# Thermostat.net
KiCad netlist of a schematic drawn in Altium Designer
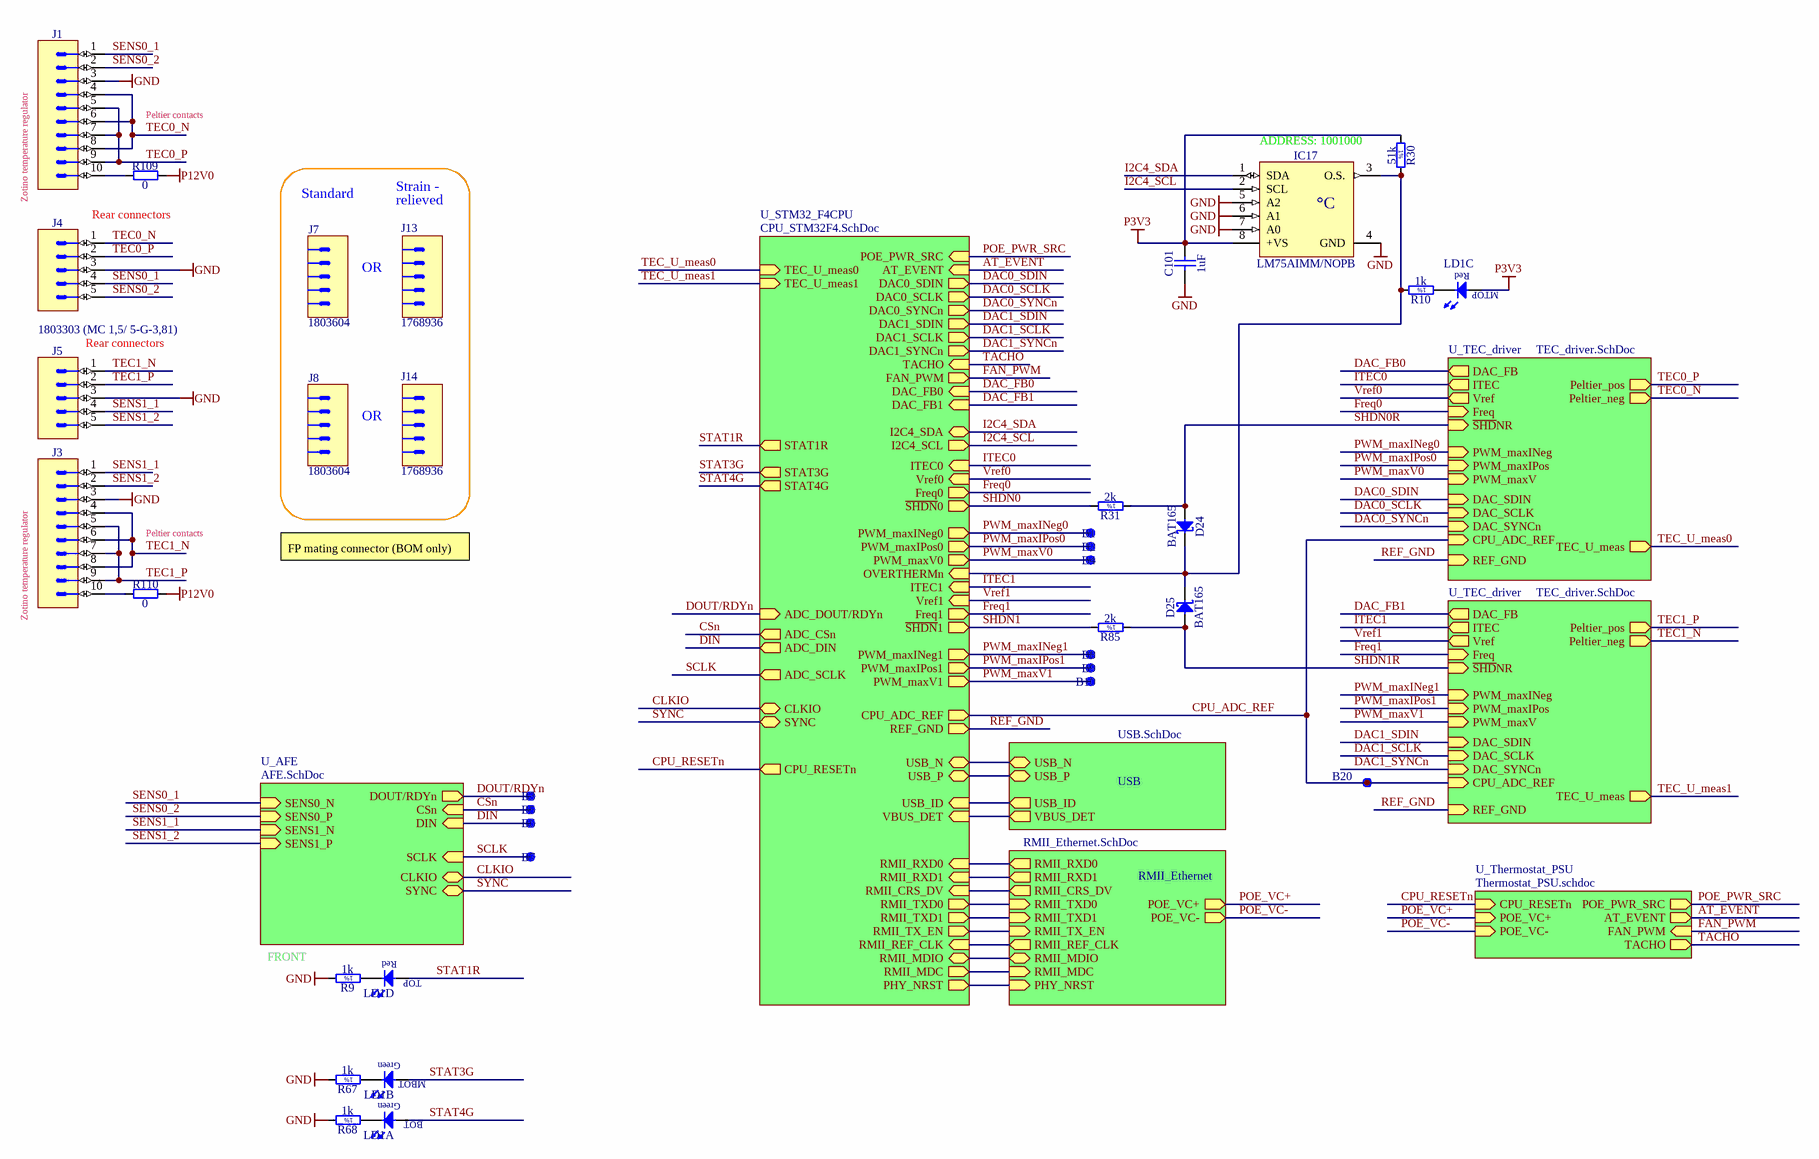
[diagram p0: Thermostat.schdoc]

(export (version "E")
  (design (tool "Eeschema 10.0.6"))
  (components
    (comp (ref "B1")
      (value "SMD Pad")
      (footprint "C100")
      (description "Through Hole Pad")
      (fields (field (name "PART NUMBER") "SMD_PAD_D1MM") (field (name "AUTHOR") "CERN DEM JLC"))
      (libsource (lib "Eletro-mechanical") (part "Single SMD Pad (Round)"))
    )
    (comp (ref "B2")
      (value "SMD Pad")
      (footprint "C100")
      (description "Through Hole Pad")
      (fields (field (name "PART NUMBER") "SMD_PAD_D1MM") (field (name "AUTHOR") "CERN DEM JLC"))
      (libsource (lib "Eletro-mechanical") (part "Single SMD Pad (Round)"))
    )
    (comp (ref "B3")
      (value "SMD Pad")
      (footprint "C100")
      (description "Through Hole Pad")
      (fields (field (name "PART NUMBER") "SMD_PAD_D1MM") (field (name "AUTHOR") "CERN DEM JLC"))
      (libsource (lib "Eletro-mechanical") (part "Single SMD Pad (Round)"))
    )
    (comp (ref "B4")
      (value "SMD Pad")
      (footprint "C100")
      (description "Through Hole Pad")
      (fields (field (name "PART NUMBER") "SMD_PAD_D1MM") (field (name "AUTHOR") "CERN DEM JLC"))
      (libsource (lib "Eletro-mechanical") (part "Single SMD Pad (Round)"))
    )
    (comp (ref "B5")
      (value "SMD Pad")
      (footprint "C100")
      (description "Through Hole Pad")
      (fields (field (name "PART NUMBER") "SMD_PAD_D1MM") (field (name "AUTHOR") "CERN DEM JLC"))
      (libsource (lib "Eletro-mechanical") (part "Single SMD Pad (Round)"))
    )
    (comp (ref "B6")
      (value "SMD Pad")
      (footprint "C100")
      (description "Through Hole Pad")
      (fields (field (name "PART NUMBER") "SMD_PAD_D1MM") (field (name "AUTHOR") "CERN DEM JLC"))
      (libsource (lib "Eletro-mechanical") (part "Single SMD Pad (Round)"))
    )
    (comp (ref "B7")
      (value "SMD Pad")
      (footprint "C100")
      (description "Through Hole Pad")
      (fields (field (name "PART NUMBER") "SMD_PAD_D1MM") (field (name "AUTHOR") "CERN DEM JLC"))
      (libsource (lib "Eletro-mechanical") (part "Single SMD Pad (Round)"))
    )
    (comp (ref "B8")
      (value "SMD Pad")
      (footprint "C100")
      (description "Through Hole Pad")
      (fields (field (name "PART NUMBER") "SMD_PAD_D1MM") (field (name "AUTHOR") "CERN DEM JLC"))
      (libsource (lib "Eletro-mechanical") (part "Single SMD Pad (Round)"))
    )
    (comp (ref "B9")
      (value "SMD Pad")
      (footprint "C100")
      (description "Through Hole Pad")
      (fields (field (name "PART NUMBER") "SMD_PAD_D1MM") (field (name "AUTHOR") "CERN DEM JLC"))
      (libsource (lib "Eletro-mechanical") (part "Single SMD Pad (Round)"))
    )
    (comp (ref "B10")
      (value "SMD Pad")
      (footprint "C100")
      (description "Through Hole Pad")
      (fields (field (name "PART NUMBER") "SMD_PAD_D1MM") (field (name "AUTHOR") "CERN DEM JLC"))
      (libsource (lib "Eletro-mechanical") (part "Single SMD Pad (Round)"))
    )
    (comp (ref "B20")
      (value "SMD Pad")
      (footprint "C100")
      (description "Through Hole Pad")
      (fields (field (name "PART NUMBER") "SMD_PAD_D1MM") (field (name "AUTHOR") "CERN DEM JLC"))
      (libsource (lib "Eletro-mechanical") (part "Single SMD Pad (Round)"))
    )
    (comp (ref "C101")
      (value "1uF")
      (footprint "CAPC1608X87N")
      (description "Non-polarised capacitor")
      (fields
        (field (name "PART NUMBER") "CC0603_1UF_25V_10%_X7R")
        (field (name "VOLTAGE") "25V")
        (field (name "AUTHOR") "CERN DEM JLC")
      )
      (libsource (lib "Capacitors") (part "Capacitor - non polarized"))
    )
    (comp (ref "D24")
      (value "BAT165")
      (footprint "SOD2512X110N")
      (description "Schottky Diode")
      (fields
        (field (name "VOLTAGE") "40V")
        (field (name "POWER") "750mA")
        (field (name "AUTHOR") "CERN DEM JLC")
      )
      (libsource (lib "ICs And Semiconductors") (part "Diode Schottky"))
    )
    (comp (ref "D25")
      (value "BAT165")
      (footprint "SOD2512X110N")
      (description "Schottky Diode")
      (fields
        (field (name "VOLTAGE") "40V")
        (field (name "POWER") "750mA")
        (field (name "AUTHOR") "CERN DEM JLC")
      )
      (libsource (lib "ICs And Semiconductors") (part "Diode Schottky"))
    )
    (comp (ref "IC17")
      (value "LM75AIMM/NOPB")
      (footprint "SOP65P490X109-8N")
      (description "Digital Temperature Sensor and Thermal Watchdog with Two-Wire Interface")
      (fields (field (name "MANUFACTURER") "TEXAS INSTRUMENTS") (field (name "AUTHOR") "CERN DEM JLC"))
      (libsource (lib "ICs And Semiconductors") (part "LM75"))
    )
    (comp (ref "J1")
      (value "Header 10")
      (footprint "3M_N2510-6002RB")
      (description "Connector 10 Male")
      (fields
        (field (name "PART NUMBER") "3M_N2510-6002RB")
        (field (name "MANUFACTURER") "3M")
        (field (name "AUTHOR") "CERN DEM JLC")
      )
      (libsource (lib "Connectors") (part "Connector 10 Male"))
    )
    (comp (ref "J3")
      (value "Header 10")
      (footprint "3M_N2510-6002RB")
      (description "Connector 10 Male")
      (fields
        (field (name "PART NUMBER") "3M_N2510-6002RB")
        (field (name "MANUFACTURER") "3M")
        (field (name "AUTHOR") "CERN DEM JLC")
      )
      (libsource (lib "Connectors") (part "Connector 10 Male"))
    )
    (comp (ref "J4")
      (value "PHOENIX_1803303")
      (footprint "PHOENIX_1803303")
      (description "Connector 5 Male")
      (fields
        (field (name "MANUFACTURER") "PHOENIX CONTACT")
        (field (name "MANUFACTURER PART NUMBER") "1803303 (MC 1,5/ 5-G-3,81)")
        (field (name "AUTHOR") "CERN DEM JLC")
      )
      (libsource (lib "Connectors") (part "Connector 5 Male"))
    )
    (comp (ref "J5")
      (value "PHOENIX_1803303")
      (footprint "PHOENIX_1803303")
      (description "Connector 5 Male")
      (fields
        (field (name "MANUFACTURER") "PHOENIX CONTACT")
        (field (name "MANUFACTURER PART NUMBER") "1803303 (MC 1,5/ 5-G-3,81)")
        (field (name "AUTHOR") "CERN DEM JLC")
      )
      (libsource (lib "Connectors") (part "Connector 5 Male"))
    )
    (comp (ref "J7")
      (value "1803604")
      (footprint "PHOENIX_1803604")
      (description "Phoenix Contact 3.81 pitch terminal plug, 5 ways")
      (fields
        (field (name "MANUFACTURER") "Phoenix Contact")
        (field (name "MANUFACTURER PART NUMBER") "1803604")
      )
      (libsource (lib "Connectors") (part "PHOENIX_1803604"))
    )
    (comp (ref "J8")
      (value "1803604")
      (footprint "PHOENIX_1803604")
      (description "Phoenix Contact 3.81 pitch terminal plug, 5 ways")
      (fields
        (field (name "MANUFACTURER") "Phoenix Contact")
        (field (name "MANUFACTURER PART NUMBER") "1803604")
      )
      (libsource (lib "Connectors") (part "PHOENIX_1803604"))
    )
    (comp (ref "J13")
      (value "1768936")
      (footprint "PHOENIX_1768936")
      (description "PHOENIX TB connector MC 1,5/ 5-STZ2-3,81 -")
      (fields (field (name "MANUFACTURER") "Phoenix Contact"))
      (libsource (lib "SamacSys") (part "PHOENIX_1768936"))
    )
    (comp (ref "J14")
      (value "1768936")
      (footprint "PHOENIX_1768936")
      (description "PHOENIX TB connector MC 1,5/ 5-STZ2-3,81 -")
      (fields (field (name "MANUFACTURER") "Phoenix Contact"))
      (libsource (lib "SamacSys") (part "PHOENIX_1768936"))
    )
    (comp (ref "LD1")
      (value "Green/Green/HeRed/HeRed")
      (footprint "LED_BIVAR_H485CHHGGDL")
      (description "LED x4 G-1C2A-BOT_G-3C4A_H-5C6A_H-7C8A-TOP")
      (fields
        (field (name "PART NUMBER") "LED_BIVAR_H485CHHGGDL")
        (field (name "MANUFACTURER") "BIVAR")
        (field (name "AUTHOR") "CERN DEM BC")
      )
      (libsource (lib "ICs And Semiconductors") (part "LED x4 G-1C2A-BOT_G-3C4A_H-5C6A_H-7C8A-TOP"))
    )
    (comp (ref "R9")
      (value "1k")
      (footprint "RESC1005X40N")
      (description "Resistor - 1%")
      (fields
        (field (name "PART NUMBER") "R0402_1K_1%_0.0625W_100PPM")
        (field (name "POWER") "0.0625W")
        (field (name "AUTHOR") "CERN DEM JLC")
      )
      (libsource (lib "Resistors") (part "Resistor - 1%"))
    )
    (comp (ref "R10")
      (value "1k")
      (footprint "RESC1005X40N")
      (description "Resistor - 1%")
      (fields
        (field (name "PART NUMBER") "R0402_1K_1%_0.0625W_100PPM")
        (field (name "POWER") "0.0625W")
        (field (name "AUTHOR") "CERN DEM JLC")
      )
      (libsource (lib "Resistors") (part "Resistor - 1%"))
    )
    (comp (ref "R30")
      (value "51k")
      (footprint "RESC1005X40N")
      (description "Resistor - 1%")
      (fields
        (field (name "PART NUMBER") "R0402_51K_1%_0.0625W_100PPM")
        (field (name "POWER") "0.0625W")
        (field (name "AUTHOR") "CERN DEM JLC")
      )
      (libsource (lib "Resistors") (part "Resistor - 1%"))
    )
    (comp (ref "R31")
      (value "2k")
      (footprint "RESC1005X40N")
      (description "Resistor - 1%")
      (fields
        (field (name "PART NUMBER") "R0402_2K_1%_0.0625W_100PPM")
        (field (name "POWER") "0.0625W")
        (field (name "AUTHOR") "CERN DEM JLC")
      )
      (libsource (lib "Resistors") (part "Resistor - 1%"))
    )
    (comp (ref "R67")
      (value "1k")
      (footprint "RESC1005X40N")
      (description "Resistor - 1%")
      (fields
        (field (name "PART NUMBER") "R0402_1K_1%_0.0625W_100PPM")
        (field (name "POWER") "0.0625W")
        (field (name "AUTHOR") "CERN DEM JLC")
      )
      (libsource (lib "Resistors") (part "Resistor - 1%"))
    )
    (comp (ref "R68")
      (value "1k")
      (footprint "RESC1005X40N")
      (description "Resistor - 1%")
      (fields
        (field (name "PART NUMBER") "R0402_1K_1%_0.0625W_100PPM")
        (field (name "POWER") "0.0625W")
        (field (name "AUTHOR") "CERN DEM JLC")
      )
      (libsource (lib "Resistors") (part "Resistor - 1%"))
    )
    (comp (ref "R85")
      (value "2k")
      (footprint "RESC1005X40N")
      (description "Resistor - 1%")
      (fields
        (field (name "PART NUMBER") "R0402_2K_1%_0.0625W_100PPM")
        (field (name "POWER") "0.0625W")
        (field (name "AUTHOR") "CERN DEM JLC")
      )
      (libsource (lib "Resistors") (part "Resistor - 1%"))
    )
    (comp (ref "R109")
      (value "0")
      (footprint "RESC1608X55N")
      (description "Resistor")
      (fields
        (field (name "PART NUMBER") "R0603_0R_JUMPER")
        (field (name "MANUFACTURER") "GENERIC")
        (field (name "AUTHOR") "CERN DEM JLC")
      )
      (libsource (lib "Resistors") (part "Resistor"))
    )
    (comp (ref "R110")
      (value "0")
      (footprint "RESC1608X55N")
      (description "Resistor")
      (fields
        (field (name "PART NUMBER") "R0603_0R_JUMPER")
        (field (name "MANUFACTURER") "GENERIC")
        (field (name "AUTHOR") "CERN DEM JLC")
      )
      (libsource (lib "Resistors") (part "Resistor"))
    )
  )
  (nets
    (net (code "3") (name "/CPU_ADC_REF") (class "Default")
      (node (ref "B20") (pin "1") (pinfunction "1_1") (pintype "bidirectional"))
    )
    (net (code "5") (name "/CSn") (class "Default")
      (node (ref "B5") (pin "1") (pinfunction "1_1") (pintype "bidirectional"))
    )
    (net (code "14") (name "/DIN") (class "Default")
      (node (ref "B6") (pin "1") (pinfunction "1_1") (pintype "bidirectional"))
    )
    (net (code "15") (name "/DOUT{slash}RDYn") (class "Default")
      (node (ref "B3") (pin "1") (pinfunction "1_1") (pintype "bidirectional"))
    )
    (net (code "19") (name "/I2C4_SCL") (class "Default")
      (node (ref "IC17") (pin "2") (pinfunction "SCL_2") (pintype "input"))
    )
    (net (code "20") (name "/I2C4_SDA") (class "Default")
      (node (ref "IC17") (pin "1") (pinfunction "SDA_1") (pintype "bidirectional"))
    )
    (net (code "23") (name "/OVERTHERMn") (class "Default")
      (node (ref "D24") (pin "1") (pinfunction "C_1") (pintype "passive"))
      (node (ref "D25") (pin "1") (pinfunction "C_1") (pintype "passive"))
      (node (ref "IC17") (pin "3") (pinfunction "O.S._3") (pintype "output"))
      (node (ref "R10") (pin "2") (pinfunction "2_2") (pintype "passive"))
      (node (ref "R30") (pin "2") (pinfunction "2_2") (pintype "passive"))
    )
    (net (code "28") (name "/PWM_maxINeg0") (class "Default")
      (node (ref "B1") (pin "1") (pinfunction "1_1") (pintype "bidirectional"))
    )
    (net (code "29") (name "/PWM_maxINeg1") (class "Default")
      (node (ref "B8") (pin "1") (pinfunction "1_1") (pintype "bidirectional"))
    )
    (net (code "30") (name "/PWM_maxIPos0") (class "Default")
      (node (ref "B2") (pin "1") (pinfunction "1_1") (pintype "bidirectional"))
    )
    (net (code "31") (name "/PWM_maxIPos1") (class "Default")
      (node (ref "B9") (pin "1") (pinfunction "1_1") (pintype "bidirectional"))
    )
    (net (code "32") (name "/PWM_maxV0") (class "Default")
      (node (ref "B4") (pin "1") (pinfunction "1_1") (pintype "bidirectional"))
    )
    (net (code "33") (name "/PWM_maxV1") (class "Default")
      (node (ref "B10") (pin "1") (pinfunction "1_1") (pintype "bidirectional"))
    )
    (net (code "44") (name "/SCLK") (class "Default")
      (node (ref "B7") (pin "1") (pinfunction "1_1") (pintype "bidirectional"))
    )
    (net (code "45") (name "/SENS0_1") (class "Default")
      (node (ref "J1") (pin "1") (pinfunction "1_1") (pintype "bidirectional"))
      (node (ref "J4") (pin "4") (pinfunction "4_4") (pintype "bidirectional"))
    )
    (net (code "46") (name "/SENS0_2") (class "Default")
      (node (ref "J1") (pin "2") (pinfunction "2_2") (pintype "bidirectional"))
      (node (ref "J4") (pin "5") (pinfunction "5_5") (pintype "bidirectional"))
    )
    (net (code "47") (name "/SENS1_1") (class "Default")
      (node (ref "J3") (pin "1") (pinfunction "1_1") (pintype "bidirectional"))
      (node (ref "J5") (pin "4") (pinfunction "4_4") (pintype "bidirectional"))
    )
    (net (code "48") (name "/SENS1_2") (class "Default")
      (node (ref "J3") (pin "2") (pinfunction "2_2") (pintype "bidirectional"))
      (node (ref "J5") (pin "5") (pinfunction "5_5") (pintype "bidirectional"))
    )
    (net (code "49") (name "/STAT1R") (class "Default")
      (node (ref "LD1") (pin "8") (pinfunction "A_8") (pintype "passive"))
    )
    (net (code "50") (name "/STAT3G") (class "Default")
      (node (ref "LD1") (pin "4") (pinfunction "A_4") (pintype "passive"))
    )
    (net (code "51") (name "/STAT4G") (class "Default")
      (node (ref "LD1") (pin "2") (pinfunction "A_2") (pintype "passive"))
    )
    (net (code "54") (name "/TEC0_N") (class "Default")
      (node (ref "J1") (pin "4") (pinfunction "4_4") (pintype "bidirectional"))
      (node (ref "J1") (pin "6") (pinfunction "6_6") (pintype "bidirectional"))
      (node (ref "J1") (pin "8") (pinfunction "8_8") (pintype "bidirectional"))
      (node (ref "J4") (pin "1") (pinfunction "1_1") (pintype "bidirectional"))
    )
    (net (code "55") (name "/TEC0_P") (class "Default")
      (node (ref "J1") (pin "5") (pinfunction "5_5") (pintype "bidirectional"))
      (node (ref "J1") (pin "7") (pinfunction "7_7") (pintype "bidirectional"))
      (node (ref "J1") (pin "9") (pinfunction "9_9") (pintype "bidirectional"))
      (node (ref "J4") (pin "2") (pinfunction "2_2") (pintype "bidirectional"))
    )
    (net (code "56") (name "/TEC1_N") (class "Default")
      (node (ref "J3") (pin "4") (pinfunction "4_4") (pintype "bidirectional"))
      (node (ref "J3") (pin "6") (pinfunction "6_6") (pintype "bidirectional"))
      (node (ref "J3") (pin "8") (pinfunction "8_8") (pintype "bidirectional"))
      (node (ref "J5") (pin "1") (pinfunction "1_1") (pintype "bidirectional"))
    )
    (net (code "57") (name "/TEC1_P") (class "Default")
      (node (ref "J3") (pin "5") (pinfunction "5_5") (pintype "bidirectional"))
      (node (ref "J3") (pin "7") (pinfunction "7_7") (pintype "bidirectional"))
      (node (ref "J3") (pin "9") (pinfunction "9_9") (pintype "bidirectional"))
      (node (ref "J5") (pin "2") (pinfunction "2_2") (pintype "bidirectional"))
    )
    (net (code "66") (name "/~{SHDN}0") (class "Default")
      (node (ref "R31") (pin "2") (pinfunction "2_2") (pintype "passive"))
    )
    (net (code "67") (name "/~{SHDN}0R") (class "Default")
      (node (ref "D24") (pin "2") (pinfunction "A_2") (pintype "passive"))
      (node (ref "R31") (pin "1") (pinfunction "1_1") (pintype "passive"))
    )
    (net (code "68") (name "/~{SHDN}1") (class "Default")
      (node (ref "R85") (pin "2") (pinfunction "2_2") (pintype "passive"))
    )
    (net (code "69") (name "/~{SHDN}1R") (class "Default")
      (node (ref "D25") (pin "2") (pinfunction "A_2") (pintype "passive"))
      (node (ref "R85") (pin "1") (pinfunction "1_1") (pintype "passive"))
    )
    (net (code "70") (name "GND") (class "Default")
      (node (ref "C101") (pin "1") (pinfunction "1_1") (pintype "passive"))
      (node (ref "IC17") (pin "4") (pinfunction "GND_4") (pintype "power_in"))
      (node (ref "IC17") (pin "5") (pinfunction "A2_5") (pintype "input"))
      (node (ref "IC17") (pin "6") (pinfunction "A1_6") (pintype "input"))
      (node (ref "IC17") (pin "7") (pinfunction "A0_7") (pintype "input"))
      (node (ref "J1") (pin "3") (pinfunction "3_3") (pintype "bidirectional"))
      (node (ref "J3") (pin "3") (pinfunction "3_3") (pintype "bidirectional"))
      (node (ref "J4") (pin "3") (pinfunction "3_3") (pintype "bidirectional"))
      (node (ref "J5") (pin "3") (pinfunction "3_3") (pintype "bidirectional"))
      (node (ref "R67") (pin "2") (pinfunction "2_2") (pintype "passive"))
      (node (ref "R68") (pin "2") (pinfunction "2_2") (pintype "passive"))
      (node (ref "R9") (pin "2") (pinfunction "2_2") (pintype "passive"))
    )
    (net (code "71") (name "Net-(J1-Pad10)") (class "Default")
      (node (ref "J1") (pin "10") (pinfunction "10_10") (pintype "bidirectional"))
      (node (ref "R109") (pin "1") (pinfunction "1_1") (pintype "passive"))
    )
    (net (code "72") (name "Net-(J3-Pad10)") (class "Default")
      (node (ref "J3") (pin "10") (pinfunction "10_10") (pintype "bidirectional"))
      (node (ref "R110") (pin "1") (pinfunction "1_1") (pintype "passive"))
    )
    (net (code "73") (name "Net-(LD1A-C)") (class "Default")
      (node (ref "LD1") (pin "1") (pinfunction "C_1") (pintype "passive"))
      (node (ref "R68") (pin "1") (pinfunction "1_1") (pintype "passive"))
    )
    (net (code "74") (name "Net-(LD1B-C)") (class "Default")
      (node (ref "LD1") (pin "3") (pinfunction "C_3") (pintype "passive"))
      (node (ref "R67") (pin "1") (pinfunction "1_1") (pintype "passive"))
    )
    (net (code "75") (name "Net-(LD1C-C)") (class "Default")
      (node (ref "LD1") (pin "5") (pinfunction "C_5") (pintype "passive"))
      (node (ref "R10") (pin "1") (pinfunction "1_1") (pintype "passive"))
    )
    (net (code "76") (name "Net-(LD1D-C)") (class "Default")
      (node (ref "LD1") (pin "7") (pinfunction "C_7") (pintype "passive"))
      (node (ref "R9") (pin "1") (pinfunction "1_1") (pintype "passive"))
    )
    (net (code "77") (name "P3V3") (class "Default")
      (node (ref "C101") (pin "2") (pinfunction "2_2") (pintype "passive"))
      (node (ref "IC17") (pin "8") (pinfunction "+VS_8") (pintype "power_in"))
      (node (ref "LD1") (pin "6") (pinfunction "A_6") (pintype "passive"))
      (node (ref "R30") (pin "1") (pinfunction "1_1") (pintype "passive"))
    )
    (net (code "78") (name "P12V0") (class "Default")
      (node (ref "R109") (pin "2") (pinfunction "2_2") (pintype "passive"))
      (node (ref "R110") (pin "2") (pinfunction "2_2") (pintype "passive"))
    )
  )
)
